# 1-Schematic_ArduinoMini.net
KiCad netlist of a schematic drawn in EasyEDA
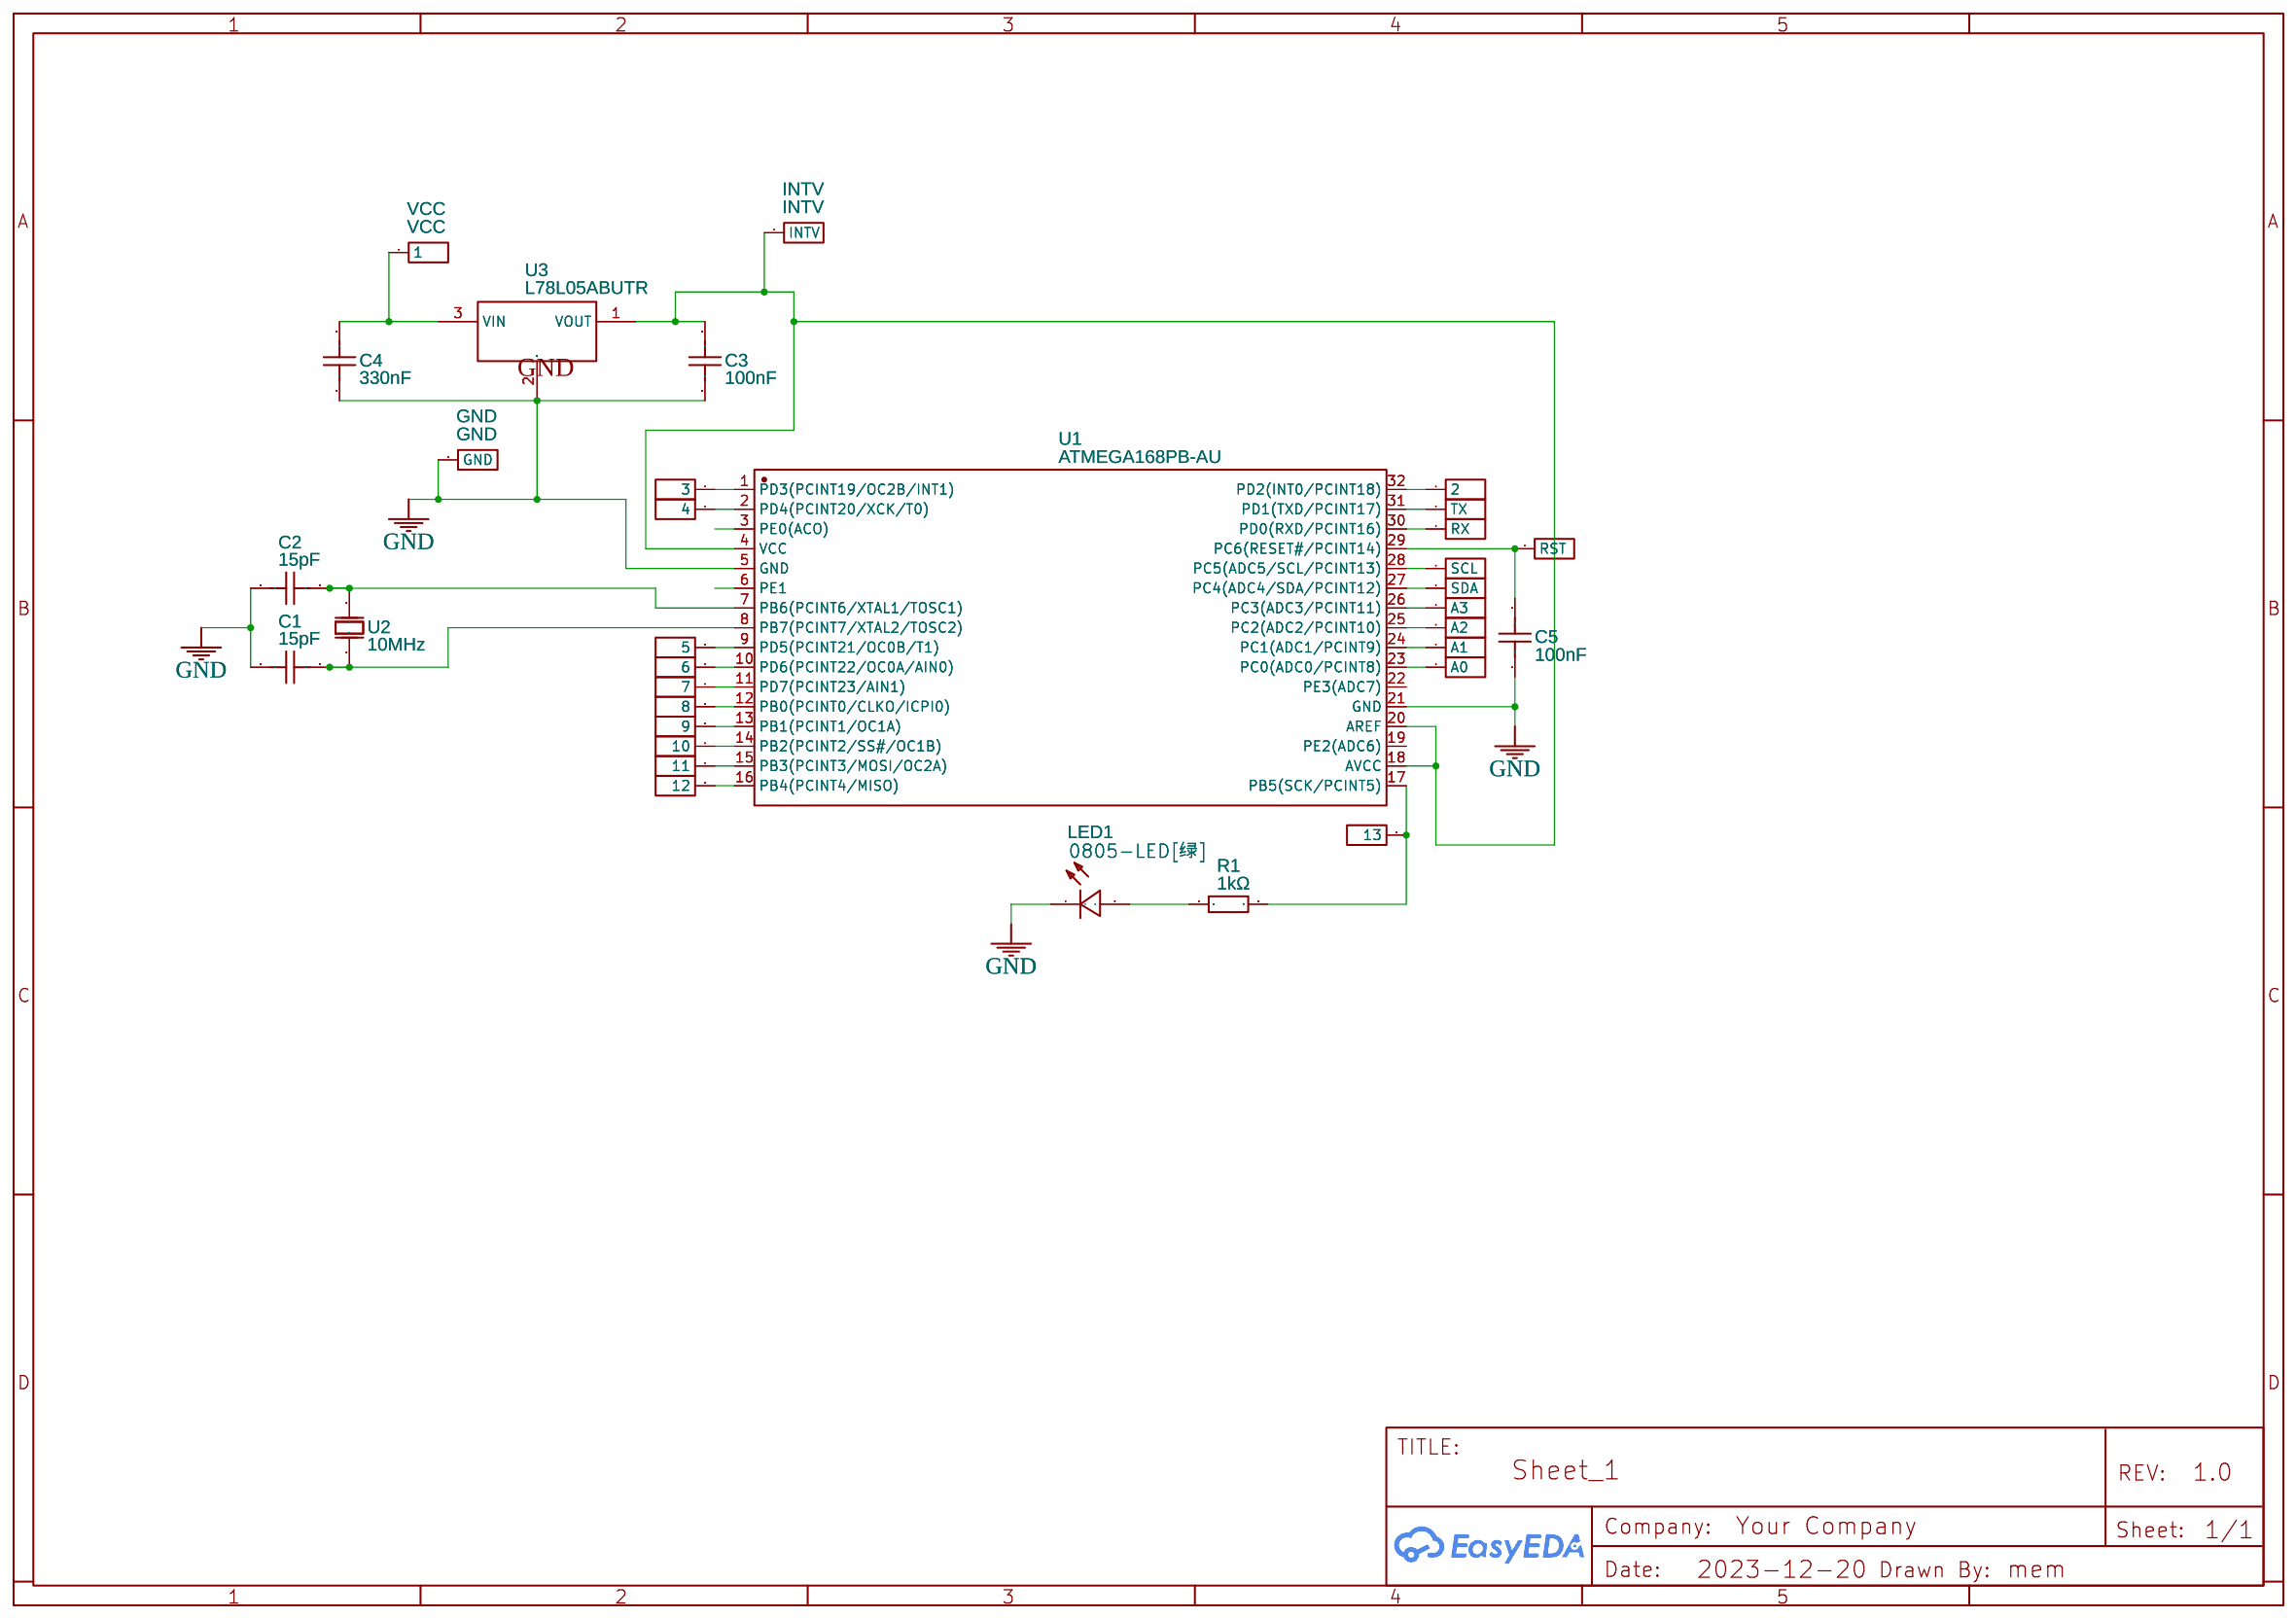
[diagram p0: schematic sheet]

(export (version "E")
  (design (tool "Eeschema 10.0.6"))
  (components
    (comp (ref "2") (value "2") (libsource (lib "") (part "HDR-M-2.54_1x1_16")))
    (comp (ref "3") (value "3") (libsource (lib "") (part "HDR-M-2.54_1x1_19")))
    (comp (ref "4") (value "4") (libsource (lib "") (part "HDR-M-2.54_1x1_1")))
    (comp (ref "5") (value "5") (libsource (lib "") (part "HDR-M-2.54_1x1_13")))
    (comp (ref "6") (value "6") (libsource (lib "") (part "HDR-M-2.54_1x1_5")))
    (comp (ref "7") (value "7") (libsource (lib "") (part "HDR-M-2.54_1x1")))
    (comp (ref "8") (value "8") (libsource (lib "") (part "HDR-M-2.54_1x1_12")))
    (comp (ref "9") (value "9") (libsource (lib "") (part "HDR-M-2.54_1x1_15")))
    (comp (ref "10") (value "10") (libsource (lib "") (part "HDR-M-2.54_1x1_7")))
    (comp (ref "11") (value "11") (libsource (lib "") (part "HDR-M-2.54_1x1_17")))
    (comp (ref "12") (value "12") (libsource (lib "") (part "HDR-M-2.54_1x1_9")))
    (comp (ref "13") (value "13") (libsource (lib "") (part "HDR-M-2.54_1x1_6")))
    (comp (ref "A0") (value "A0") (libsource (lib "") (part "HDR-M-2.54_1x1_3")))
    (comp (ref "A1") (value "A1") (libsource (lib "") (part "HDR-M-2.54_1x1_20")))
    (comp (ref "A2") (value "A2") (libsource (lib "") (part "HDR-M-2.54_1x1_21")))
    (comp (ref "A3") (value "A3") (libsource (lib "") (part "HDR-M-2.54_1x1_4")))
    (comp (ref "C1")
      (value "15pF")
      (fields
        (field (name "Manufacturer Part") "C0805C150K3HAC7800")
        (field (name "Manufacturer") "KEMET(基美)")
      )
      (libsource (lib "") (part "C0805C150K3HAC7800"))
    )
    (comp (ref "C2")
      (value "15pF")
      (fields
        (field (name "Manufacturer Part") "C0805C150K3HAC7800")
        (field (name "Manufacturer") "KEMET(基美)")
      )
      (libsource (lib "") (part "C0805C150K3HAC7800"))
    )
    (comp (ref "C3")
      (value "100nF")
      (fields (field (name "Manufacturer Part") "08051C104KAZ2A") (field (name "Manufacturer") "Kyocera AVX"))
      (libsource (lib "") (part "08051C104KAZ2A"))
    )
    (comp (ref "C4")
      (value "330nF")
      (fields
        (field (name "Manufacturer Part") "CC0805KKX7R7BB334")
        (field (name "Manufacturer") "YAGEO(国巨)")
      )
      (libsource (lib "") (part "CC0805KKX7R7BB334"))
    )
    (comp (ref "C5")
      (value "100nF")
      (fields (field (name "Manufacturer Part") "08051C104KAZ2A") (field (name "Manufacturer") "Kyocera AVX"))
      (libsource (lib "") (part "08051C104KAZ2A"))
    )
    (comp (ref "GND") (value "GND") (libsource (lib "") (part "HDR-M-2.54_1x1_22")))
    (comp (ref "INTV") (value "INTV") (libsource (lib "") (part "HDR-M-2.54_1x1_8")))
    (comp (ref "LED1") (value "0805-LED[绿]") (libsource (lib "") (part "0805-LED[绿]")))
    (comp (ref "R1")
      (value "1kΩ")
      (fields
        (field (name "Manufacturer Part") "0805W8F1001T5E")
        (field (name "Manufacturer") "UNI-ROYAL(厚声)")
      )
      (libsource (lib "") (part "0805W8F1001T5E"))
    )
    (comp (ref "RST") (value "RST") (libsource (lib "") (part "HDR-M-2.54_1x1_11")))
    (comp (ref "RX") (value "RX") (libsource (lib "") (part "HDR-M-2.54_1x1_10")))
    (comp (ref "SCL") (value "SCL") (libsource (lib "") (part "HDR-M-2.54_1x1_18")))
    (comp (ref "SDA") (value "SDA") (libsource (lib "") (part "HDR-M-2.54_1x1_14")))
    (comp (ref "TX") (value "TX") (libsource (lib "") (part "HDR-M-2.54_1x1_23")))
    (comp (ref "U1")
      (value "ATMEGA168PB-AU")
      (fields (field (name "Manufacturer") "MICROCHIP(美国微芯)"))
      (libsource (lib "") (part "ATMEGA168PB-AU"))
    )
    (comp (ref "U2")
      (value "10MHz")
      (fields (field (name "Manufacturer Part") "ATS100B-E") (field (name "Manufacturer") "CTS(西迪斯)"))
      (libsource (lib "") (part "ATS100B-E"))
    )
    (comp (ref "U3")
      (value "L78L05ABUTR")
      (fields (field (name "Manufacturer") "ST(意法半导体)"))
      (libsource (lib "") (part "L78L05ABUTR"))
    )
    (comp (ref "VCC") (value "VCC") (libsource (lib "") (part "HDR-M-2.54_1x1_2")))
  )
  (nets
    (net (code "1") (name "GND") (class "Default")
      (node (ref "C1") (pin "1") (pinfunction "1_1") (pintype "unspecified"))
      (node (ref "C2") (pin "1") (pinfunction "1_1") (pintype "unspecified"))
      (node (ref "C3") (pin "1") (pinfunction "1_1") (pintype "unspecified"))
      (node (ref "C4") (pin "1") (pinfunction "1_1") (pintype "unspecified"))
      (node (ref "C5") (pin "1") (pinfunction "1_1") (pintype "unspecified"))
      (node (ref "GND") (pin "1") (pinfunction "GND_1") (pintype "input"))
      (node (ref "LED1") (pin "1") (pinfunction "-_1") (pintype "unspecified"))
      (node (ref "U1") (pin "21") (pinfunction "GND_21") (pintype "unspecified"))
      (node (ref "U1") (pin "5") (pinfunction "GND_5") (pintype "unspecified"))
      (node (ref "U3") (pin "2") (pinfunction "GND_2") (pintype "passive"))
    )
    (net (code "2") (name "Net-(2-2)") (class "Default")
      (node (ref "2") (pin "1") (pinfunction "2_1") (pintype "input"))
      (node (ref "U1") (pin "32") (pinfunction "PD2(INT0/PCINT18)_32") (pintype "unspecified"))
    )
    (net (code "3") (name "Net-(3-3)") (class "Default")
      (node (ref "3") (pin "1") (pinfunction "3_1") (pintype "input"))
      (node (ref "U1") (pin "1") (pinfunction "PD3(PCINT19/OC2B/INT1)_1") (pintype "unspecified"))
    )
    (net (code "4") (name "Net-(4-4)") (class "Default")
      (node (ref "4") (pin "1") (pinfunction "4_1") (pintype "input"))
      (node (ref "U1") (pin "2") (pinfunction "PD4(PCINT20/XCK/T0)_2") (pintype "unspecified"))
    )
    (net (code "5") (name "Net-(5-5)") (class "Default")
      (node (ref "5") (pin "1") (pinfunction "5_1") (pintype "input"))
      (node (ref "U1") (pin "9") (pinfunction "PD5(PCINT21/OC0B/T1)_9") (pintype "unspecified"))
    )
    (net (code "6") (name "Net-(6-6)") (class "Default")
      (node (ref "6") (pin "1") (pinfunction "6_1") (pintype "input"))
      (node (ref "U1") (pin "10") (pinfunction "PD6(PCINT22/OC0A/AIN0)_10") (pintype "unspecified"))
    )
    (net (code "7") (name "Net-(7-7)") (class "Default")
      (node (ref "7") (pin "1") (pinfunction "7_1") (pintype "input"))
      (node (ref "U1") (pin "11") (pinfunction "PD7(PCINT23/AIN1)_11") (pintype "unspecified"))
    )
    (net (code "8") (name "Net-(8-8)") (class "Default")
      (node (ref "8") (pin "1") (pinfunction "8_1") (pintype "input"))
      (node (ref "U1") (pin "12") (pinfunction "PB0(PCINT0/CLKO/ICPI0)_12") (pintype "unspecified"))
    )
    (net (code "9") (name "Net-(9-9)") (class "Default")
      (node (ref "9") (pin "1") (pinfunction "9_1") (pintype "input"))
      (node (ref "U1") (pin "13") (pinfunction "PB1(PCINT1/OC1A)_13") (pintype "unspecified"))
    )
    (net (code "10") (name "Net-(10-10)") (class "Default")
      (node (ref "10") (pin "1") (pinfunction "10_1") (pintype "input"))
      (node (ref "U1") (pin "14") (pinfunction "PB2(PCINT2/SS#/OC1B)_14") (pintype "unspecified"))
    )
    (net (code "11") (name "Net-(11-11)") (class "Default")
      (node (ref "11") (pin "1") (pinfunction "11_1") (pintype "input"))
      (node (ref "U1") (pin "15") (pinfunction "PB3(PCINT3/MOSI/OC2A)_15") (pintype "unspecified"))
    )
    (net (code "12") (name "Net-(12-12)") (class "Default")
      (node (ref "12") (pin "1") (pinfunction "12_1") (pintype "input"))
      (node (ref "U1") (pin "16") (pinfunction "PB4(PCINT4/MISO)_16") (pintype "unspecified"))
    )
    (net (code "13") (name "Net-(13-13)") (class "Default")
      (node (ref "13") (pin "1") (pinfunction "13_1") (pintype "input"))
      (node (ref "R1") (pin "2") (pinfunction "2_2") (pintype "input"))
      (node (ref "U1") (pin "17") (pinfunction "PB5(SCK/PCINT5)_17") (pintype "unspecified"))
    )
    (net (code "14") (name "Net-(A0-A0)") (class "Default")
      (node (ref "A0") (pin "1") (pinfunction "A0_1") (pintype "input"))
      (node (ref "U1") (pin "23") (pinfunction "PC0(ADC0/PCINT8)_23") (pintype "unspecified"))
    )
    (net (code "15") (name "Net-(A1-A1)") (class "Default")
      (node (ref "A1") (pin "1") (pinfunction "A1_1") (pintype "input"))
      (node (ref "U1") (pin "24") (pinfunction "PC1(ADC1/PCINT9)_24") (pintype "unspecified"))
    )
    (net (code "16") (name "Net-(A2-A2)") (class "Default")
      (node (ref "A2") (pin "1") (pinfunction "A2_1") (pintype "input"))
      (node (ref "U1") (pin "25") (pinfunction "PC2(ADC2/PCINT10)_25") (pintype "unspecified"))
    )
    (net (code "17") (name "Net-(A3-A3)") (class "Default")
      (node (ref "A3") (pin "1") (pinfunction "A3_1") (pintype "input"))
      (node (ref "U1") (pin "26") (pinfunction "PC3(ADC3/PCINT11)_26") (pintype "unspecified"))
    )
    (net (code "18") (name "Net-(INTV-INTV)") (class "Default")
      (node (ref "C3") (pin "2") (pinfunction "2_2") (pintype "unspecified"))
      (node (ref "INTV") (pin "1") (pinfunction "INTV_1") (pintype "input"))
      (node (ref "U1") (pin "18") (pinfunction "AVCC_18") (pintype "unspecified"))
      (node (ref "U1") (pin "20") (pinfunction "AREF_20") (pintype "unspecified"))
      (node (ref "U1") (pin "4") (pinfunction "VCC_4") (pintype "unspecified"))
      (node (ref "U3") (pin "1") (pinfunction "VOUT_1") (pintype "passive"))
    )
    (net (code "19") (name "Net-(LED1-+)") (class "Default")
      (node (ref "LED1") (pin "2") (pinfunction "+_2") (pintype "unspecified"))
      (node (ref "R1") (pin "1") (pinfunction "1_1") (pintype "input"))
    )
    (net (code "20") (name "Net-(RST-RST)") (class "Default")
      (node (ref "C5") (pin "2") (pinfunction "2_2") (pintype "unspecified"))
      (node (ref "RST") (pin "1") (pinfunction "RST_1") (pintype "input"))
      (node (ref "U1") (pin "29") (pinfunction "PC6(RESET#/PCINT14)_29") (pintype "unspecified"))
    )
    (net (code "21") (name "Net-(RX-RX)") (class "Default")
      (node (ref "RX") (pin "1") (pinfunction "RX_1") (pintype "input"))
      (node (ref "U1") (pin "30") (pinfunction "PD0(RXD/PCINT16)_30") (pintype "unspecified"))
    )
    (net (code "22") (name "Net-(SCL-SCL)") (class "Default")
      (node (ref "SCL") (pin "1") (pinfunction "SCL_1") (pintype "input"))
      (node (ref "U1") (pin "28") (pinfunction "PC5(ADC5/SCL/PCINT13)_28") (pintype "unspecified"))
    )
    (net (code "23") (name "Net-(SDA-SDA)") (class "Default")
      (node (ref "SDA") (pin "1") (pinfunction "SDA_1") (pintype "input"))
      (node (ref "U1") (pin "27") (pinfunction "PC4(ADC4/SDA/PCINT12)_27") (pintype "unspecified"))
    )
    (net (code "24") (name "Net-(TX-TX)") (class "Default")
      (node (ref "TX") (pin "1") (pinfunction "TX_1") (pintype "input"))
      (node (ref "U1") (pin "31") (pinfunction "PD1(TXD/PCINT17)_31") (pintype "unspecified"))
    )
    (net (code "25") (name "Net-(U1-PB6(PCINT6{slash}XTAL1{slash}TOSC1))") (class "Default")
      (node (ref "C2") (pin "2") (pinfunction "2_2") (pintype "unspecified"))
      (node (ref "U1") (pin "7") (pinfunction "PB6(PCINT6/XTAL1/TOSC1)_7") (pintype "unspecified"))
      (node (ref "U2") (pin "2") (pinfunction "2_2") (pintype "input"))
    )
    (net (code "26") (name "Net-(U1-PB7(PCINT7{slash}XTAL2{slash}TOSC2))") (class "Default")
      (node (ref "C1") (pin "2") (pinfunction "2_2") (pintype "unspecified"))
      (node (ref "U1") (pin "8") (pinfunction "PB7(PCINT7/XTAL2/TOSC2)_8") (pintype "unspecified"))
      (node (ref "U2") (pin "1") (pinfunction "1_1") (pintype "input"))
    )
    (net (code "27") (name "Net-(U3-VIN)") (class "Default")
      (node (ref "C4") (pin "2") (pinfunction "2_2") (pintype "unspecified"))
      (node (ref "U3") (pin "3") (pinfunction "VIN_3") (pintype "passive"))
      (node (ref "VCC") (pin "1") (pinfunction "1_1") (pintype "input"))
    )
    (net (code "28") (name "unconnected-(U1-PE0(ACO)-Pad3)") (class "Default")
      (node (ref "U1") (pin "3") (pinfunction "PE0(ACO)_3") (pintype "unspecified"))
    )
    (net (code "29") (name "unconnected-(U1-PE1-Pad6)") (class "Default")
      (node (ref "U1") (pin "6") (pinfunction "PE1_6") (pintype "unspecified"))
    )
    (net (code "30") (name "unconnected-(U1-PE2(ADC6)-Pad19)") (class "Default")
      (node (ref "U1") (pin "19") (pinfunction "PE2(ADC6)_19") (pintype "unspecified"))
    )
    (net (code "31") (name "unconnected-(U1-PE3(ADC7)-Pad22)") (class "Default")
      (node (ref "U1") (pin "22") (pinfunction "PE3(ADC7)_22") (pintype "unspecified"))
    )
  )
)
